# lpc11c14.net
KiCad netlist of a schematic drawn in Altium Designer
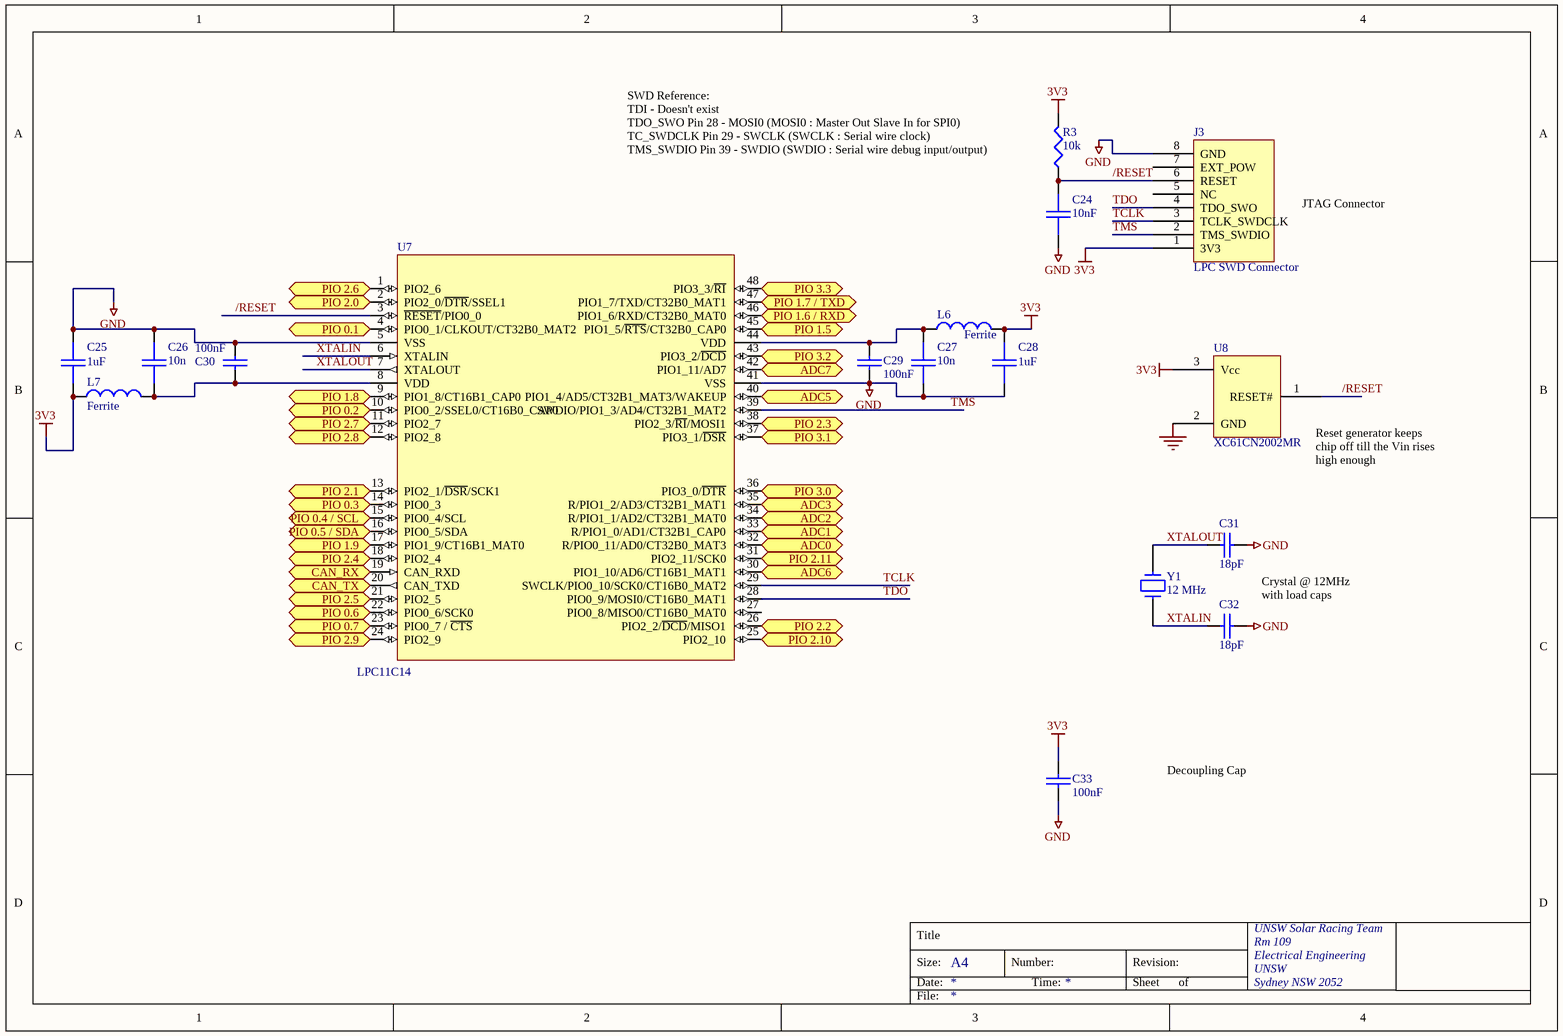
[diagram p0: lpc11c14.SchDoc]

(export (version "E")
  (design (tool "Eeschema 10.0.6"))
  (components
    (comp (ref "C24")
      (value "10nF")
      (footprint "0603")
      (description "Capacitor")
      (libsource (lib "SunswiftLib20030312RR") (part "CAP"))
    )
    (comp (ref "C25")
      (value "1uF")
      (footprint "0603")
      (description "Capacitor")
      (fields (field (name "Comment") "1u"))
      (libsource (lib "RCLDQ") (part "CAP"))
    )
    (comp (ref "C26")
      (value "10n")
      (footprint "0603")
      (description "Capacitor")
      (libsource (lib "2009_BatteryMaster") (part "CAP"))
    )
    (comp (ref "C27")
      (value "10n")
      (footprint "0603")
      (description "Capacitor")
      (libsource (lib "2009_BatteryMaster") (part "CAP"))
    )
    (comp (ref "C28")
      (value "1uF")
      (footprint "0603")
      (description "Capacitor")
      (fields (field (name "Comment") "1u"))
      (libsource (lib "RCLDQ") (part "CAP"))
    )
    (comp (ref "C29")
      (value "100nF")
      (footprint "0603")
      (description "Capacitor")
      (libsource (lib "*") (part "CAP"))
    )
    (comp (ref "C30")
      (value "100nF")
      (footprint "0603")
      (description "Capacitor")
      (libsource (lib "*") (part "CAP"))
    )
    (comp (ref "C31")
      (value "18pF")
      (footprint "0603")
      (description "Capacitor")
      (libsource (lib "*") (part "CAP"))
    )
    (comp (ref "C32")
      (value "18pF")
      (footprint "0603")
      (description "Capacitor")
      (libsource (lib "*") (part "CAP"))
    )
    (comp (ref "C33")
      (value "100nF")
      (footprint "0603")
      (description "Capacitor")
      (libsource (lib "*") (part "CAP"))
    )
    (comp (ref "J3")
      (value "LPC SWD Connector")
      (footprint "IDC8")
      (libsource (lib "2009_BatteryMaster") (part "LPCLink_Connector"))
    )
    (comp (ref "L6")
      (value "Ferrite")
      (footprint "0603")
      (description "Inductor")
      (fields (field (name "MANUFACTURER") "Generic Components") (field (name "PUBLISHER") "Altium Limited"))
      (libsource (lib "RCLDQ") (part "INDUCTOR"))
    )
    (comp (ref "L7")
      (value "Ferrite")
      (footprint "0603")
      (description "Inductor")
      (fields (field (name "MANUFACTURER") "Generic Components") (field (name "PUBLISHER") "Altium Limited"))
      (libsource (lib "RCLDQ") (part "INDUCTOR"))
    )
    (comp (ref "R3")
      (value "10k")
      (footprint "0603")
      (description "Resistor")
      (libsource (lib "SunswiftLib20030312RR") (part "RES1"))
    )
    (comp (ref "U7")
      (value "LPC11C14")
      (footprint "TSQFP50P900X900-48N")
      (libsource (lib "LPC") (part "LPC11C14_Full"))
    )
    (comp (ref "U8")
      (value "XC61CN2002MR")
      (footprint "SOT23(3)")
      (description "SOT23 reset generator")
      (libsource (lib "*") (part "XC61F"))
    )
    (comp (ref "Y1")
      (value "12 MHz")
      (footprint "HC49/4H")
      (description "Crystal")
      (libsource (lib "*") (part "CRYSTAL"))
    )
  )
  (nets
    (net (code "1") (name "/ADC0") (class "Default")
      (node (ref "U7") (pin "32") (pinfunction "R/PIO0_11/AD0/CT32B0_MAT3_32") (pintype "bidirectional"))
    )
    (net (code "2") (name "/ADC1") (class "Default")
      (node (ref "U7") (pin "33") (pinfunction "R/PIO1_0/AD1/CT32B1_CAP0_33") (pintype "bidirectional"))
    )
    (net (code "3") (name "/ADC2") (class "Default")
      (node (ref "U7") (pin "34") (pinfunction "R/PIO1_1/AD2/CT32B1_MAT0_34") (pintype "bidirectional"))
    )
    (net (code "4") (name "/ADC3") (class "Default")
      (node (ref "U7") (pin "35") (pinfunction "R/PIO1_2/AD3/CT32B1_MAT1_35") (pintype "bidirectional"))
    )
    (net (code "5") (name "/ADC5") (class "Default")
      (node (ref "U7") (pin "40") (pinfunction "PIO1_4/AD5/CT32B1_MAT3/WAKEUP_40") (pintype "bidirectional"))
    )
    (net (code "6") (name "/ADC6") (class "Default")
      (node (ref "U7") (pin "30") (pinfunction "PIO1_10/AD6/CT16B1_MAT1_30") (pintype "bidirectional"))
    )
    (net (code "7") (name "/ADC7") (class "Default")
      (node (ref "U7") (pin "42") (pinfunction "PIO1_11/AD7_42") (pintype "bidirectional"))
    )
    (net (code "8") (name "/CAN_RX") (class "Default")
      (node (ref "U7") (pin "19") (pinfunction "CAN_RXD_19") (pintype "input"))
    )
    (net (code "9") (name "/CAN_TX") (class "Default")
      (node (ref "U7") (pin "20") (pinfunction "CAN_TXD_20") (pintype "output"))
    )
    (net (code "10") (name "/PIO 0.1") (class "Default")
      (node (ref "U7") (pin "4") (pinfunction "PIO0_1/CLKOUT/CT32B0_MAT2_4") (pintype "bidirectional"))
    )
    (net (code "11") (name "/PIO 0.2") (class "Default")
      (node (ref "U7") (pin "10") (pinfunction "PIO0_2/SSEL0/CT16B0_CAP0_10") (pintype "bidirectional"))
    )
    (net (code "12") (name "/PIO 0.3") (class "Default")
      (node (ref "U7") (pin "14") (pinfunction "PIO0_3_14") (pintype "bidirectional"))
    )
    (net (code "13") (name "/PIO 0.4 {slash} SCL") (class "Default")
      (node (ref "U7") (pin "15") (pinfunction "PIO0_4/SCL_15") (pintype "bidirectional"))
    )
    (net (code "14") (name "/PIO 0.5 {slash} SDA") (class "Default")
      (node (ref "U7") (pin "16") (pinfunction "PIO0_5/SDA_16") (pintype "bidirectional"))
    )
    (net (code "15") (name "/PIO 0.6") (class "Default")
      (node (ref "U7") (pin "22") (pinfunction "PIO0_6/SCK0_22") (pintype "bidirectional"))
    )
    (net (code "16") (name "/PIO 0.7") (class "Default")
      (node (ref "U7") (pin "23") (pinfunction "PIO0_7_/_~{CTS}_23") (pintype "bidirectional"))
    )
    (net (code "17") (name "/PIO 1.5") (class "Default")
      (node (ref "U7") (pin "45") (pinfunction "PIO1_5/~{RTS}/CT32B0_CAP0_45") (pintype "bidirectional"))
    )
    (net (code "18") (name "/PIO 1.6 {slash} RXD") (class "Default")
      (node (ref "U7") (pin "46") (pinfunction "PIO1_6/RXD/CT32B0_MAT0_46") (pintype "bidirectional"))
    )
    (net (code "19") (name "/PIO 1.7 {slash} TXD") (class "Default")
      (node (ref "U7") (pin "47") (pinfunction "PIO1_7/TXD/CT32B0_MAT1_47") (pintype "bidirectional"))
    )
    (net (code "20") (name "/PIO 1.8") (class "Default")
      (node (ref "U7") (pin "9") (pinfunction "PIO1_8/CT16B1_CAP0_9") (pintype "bidirectional"))
    )
    (net (code "21") (name "/PIO 1.9") (class "Default")
      (node (ref "U7") (pin "17") (pinfunction "PIO1_9/CT16B1_MAT0_17") (pintype "bidirectional"))
    )
    (net (code "22") (name "/PIO 2.0") (class "Default")
      (node (ref "U7") (pin "2") (pinfunction "PIO2_0/~{DTR}/SSEL1_2") (pintype "bidirectional"))
    )
    (net (code "23") (name "/PIO 2.1") (class "Default")
      (node (ref "U7") (pin "13") (pinfunction "PIO2_1/~{DSR}/SCK1_13") (pintype "bidirectional"))
    )
    (net (code "24") (name "/PIO 2.2") (class "Default")
      (node (ref "U7") (pin "26") (pinfunction "PIO2_2/~{DCD}/MISO1_26") (pintype "bidirectional"))
    )
    (net (code "25") (name "/PIO 2.3") (class "Default")
      (node (ref "U7") (pin "38") (pinfunction "PIO2_3/~{RI}/MOSI1_38") (pintype "bidirectional"))
    )
    (net (code "26") (name "/PIO 2.4") (class "Default")
      (node (ref "U7") (pin "18") (pinfunction "PIO2_4_18") (pintype "bidirectional"))
    )
    (net (code "27") (name "/PIO 2.5") (class "Default")
      (node (ref "U7") (pin "21") (pinfunction "PIO2_5_21") (pintype "bidirectional"))
    )
    (net (code "28") (name "/PIO 2.6") (class "Default")
      (node (ref "U7") (pin "1") (pinfunction "PIO2_6_1") (pintype "bidirectional"))
    )
    (net (code "29") (name "/PIO 2.7") (class "Default")
      (node (ref "U7") (pin "11") (pinfunction "PIO2_7_11") (pintype "bidirectional"))
    )
    (net (code "30") (name "/PIO 2.8") (class "Default")
      (node (ref "U7") (pin "12") (pinfunction "PIO2_8_12") (pintype "bidirectional"))
    )
    (net (code "31") (name "/PIO 2.9") (class "Default")
      (node (ref "U7") (pin "24") (pinfunction "PIO2_9_24") (pintype "bidirectional"))
    )
    (net (code "32") (name "/PIO 2.10") (class "Default")
      (node (ref "U7") (pin "25") (pinfunction "PIO2_10_25") (pintype "bidirectional"))
    )
    (net (code "33") (name "/PIO 2.11") (class "Default")
      (node (ref "U7") (pin "31") (pinfunction "PIO2_11/SCK0_31") (pintype "bidirectional"))
    )
    (net (code "34") (name "/PIO 3.0") (class "Default")
      (node (ref "U7") (pin "36") (pinfunction "PIO3_0/~{DTR}_36") (pintype "bidirectional"))
    )
    (net (code "35") (name "/PIO 3.1") (class "Default")
      (node (ref "U7") (pin "37") (pinfunction "PIO3_1/~{DSR}_37") (pintype "bidirectional"))
    )
    (net (code "36") (name "/PIO 3.2") (class "Default")
      (node (ref "U7") (pin "43") (pinfunction "PIO3_2/~{DCD}_43") (pintype "bidirectional"))
    )
    (net (code "37") (name "/PIO 3.3") (class "Default")
      (node (ref "U7") (pin "48") (pinfunction "PIO3_3/~{RI}_48") (pintype "bidirectional"))
    )
    (net (code "38") (name "/TCLK") (class "Default")
      (node (ref "J3") (pin "3") (pinfunction "TCLK_SWDCLK_3") (pintype "passive"))
      (node (ref "U7") (pin "29") (pinfunction "SWCLK/PIO0_10/SCK0/CT16B0_MAT2_29") (pintype "bidirectional"))
    )
    (net (code "39") (name "/TDO") (class "Default")
      (node (ref "J3") (pin "4") (pinfunction "TDO_SWO_4") (pintype "passive"))
      (node (ref "U7") (pin "28") (pinfunction "PIO0_9/MOSI0/CT16B0_MAT1_28") (pintype "bidirectional"))
    )
    (net (code "40") (name "/TMS") (class "Default")
      (node (ref "J3") (pin "2") (pinfunction "TMS_SWDIO_2") (pintype "passive"))
      (node (ref "U7") (pin "39") (pinfunction "SWDIO/PIO1_3/AD4/CT32B1_MAT2_39") (pintype "bidirectional"))
    )
    (net (code "41") (name "/XTALIN") (class "Default")
      (node (ref "C32") (pin "1") (pinfunction "1_1") (pintype "passive"))
      (node (ref "U7") (pin "6") (pinfunction "XTALIN_6") (pintype "input"))
      (node (ref "Y1") (pin "1") (pinfunction "1_1") (pintype "passive"))
    )
    (net (code "42") (name "/XTALOUT") (class "Default")
      (node (ref "C31") (pin "1") (pinfunction "1_1") (pintype "passive"))
      (node (ref "U7") (pin "7") (pinfunction "XTALOUT_7") (pintype "output"))
      (node (ref "Y1") (pin "2") (pinfunction "2_2") (pintype "passive"))
    )
    (net (code "43") (name "/{slash}RESET") (class "Default")
      (node (ref "C24") (pin "1") (pinfunction "1_1") (pintype "passive"))
      (node (ref "J3") (pin "6") (pinfunction "RESET_6") (pintype "passive"))
      (node (ref "R3") (pin "1") (pinfunction "1_1") (pintype "passive"))
      (node (ref "U7") (pin "3") (pinfunction "~{RESET}/PIO0_0_3") (pintype "bidirectional"))
      (node (ref "U8") (pin "1") (pinfunction "RESET#_1") (pintype "passive"))
    )
    (net (code "44") (name "3V3") (class "Default")
      (node (ref "C25") (pin "2") (pinfunction "2_2") (pintype "passive"))
      (node (ref "C28") (pin "1") (pinfunction "1_1") (pintype "passive"))
      (node (ref "C33") (pin "1") (pinfunction "1_1") (pintype "passive"))
      (node (ref "J3") (pin "1") (pinfunction "3V3_1") (pintype "passive"))
      (node (ref "L6") (pin "2") (pinfunction "2_2") (pintype "passive"))
      (node (ref "L7") (pin "1") (pinfunction "1_1") (pintype "passive"))
      (node (ref "R3") (pin "2") (pinfunction "2_2") (pintype "passive"))
      (node (ref "U8") (pin "3") (pinfunction "Vcc_3") (pintype "passive"))
    )
    (net (code "45") (name "GND") (class "Default")
      (node (ref "C24") (pin "2") (pinfunction "2_2") (pintype "passive"))
      (node (ref "C25") (pin "1") (pinfunction "1_1") (pintype "passive"))
      (node (ref "C26") (pin "1") (pinfunction "1_1") (pintype "passive"))
      (node (ref "C27") (pin "2") (pinfunction "2_2") (pintype "passive"))
      (node (ref "C28") (pin "2") (pinfunction "2_2") (pintype "passive"))
      (node (ref "C29") (pin "2") (pinfunction "2_2") (pintype "passive"))
      (node (ref "C30") (pin "1") (pinfunction "1_1") (pintype "passive"))
      (node (ref "C31") (pin "2") (pinfunction "2_2") (pintype "passive"))
      (node (ref "C32") (pin "2") (pinfunction "2_2") (pintype "passive"))
      (node (ref "C33") (pin "2") (pinfunction "2_2") (pintype "passive"))
      (node (ref "J3") (pin "8") (pinfunction "GND_8") (pintype "passive"))
      (node (ref "U7") (pin "41") (pinfunction "VSS_41") (pintype "power_in"))
      (node (ref "U7") (pin "5") (pinfunction "VSS_5") (pintype "power_in"))
      (node (ref "U8") (pin "2") (pinfunction "GND_2") (pintype "passive"))
    )
    (net (code "46") (name "Net-(C26-Pad2)") (class "Default")
      (node (ref "C26") (pin "2") (pinfunction "2_2") (pintype "passive"))
      (node (ref "C30") (pin "2") (pinfunction "2_2") (pintype "passive"))
      (node (ref "L7") (pin "2") (pinfunction "2_2") (pintype "passive"))
      (node (ref "U7") (pin "8") (pinfunction "VDD_8") (pintype "power_in"))
    )
    (net (code "47") (name "Net-(C27-Pad1)") (class "Default")
      (node (ref "C27") (pin "1") (pinfunction "1_1") (pintype "passive"))
      (node (ref "C29") (pin "1") (pinfunction "1_1") (pintype "passive"))
      (node (ref "L6") (pin "1") (pinfunction "1_1") (pintype "passive"))
      (node (ref "U7") (pin "44") (pinfunction "VDD_44") (pintype "power_in"))
    )
    (net (code "48") (name "unconnected-(J3-EXT_POW-Pad7)") (class "Default")
      (node (ref "J3") (pin "7") (pinfunction "EXT_POW_7") (pintype "passive"))
    )
    (net (code "49") (name "unconnected-(J3-NC-Pad5)") (class "Default")
      (node (ref "J3") (pin "5") (pinfunction "NC_5") (pintype "passive"))
    )
    (net (code "50") (name "unconnected-(U7-PIO0_8{slash}MISO0{slash}CT16B0_MAT0-Pad27)") (class "Default")
      (node (ref "U7") (pin "27") (pinfunction "PIO0_8/MISO0/CT16B0_MAT0_27") (pintype "bidirectional"))
    )
  )
)
